# IR_Control.net
KiCad netlist of a schematic drawn in Altium Designer
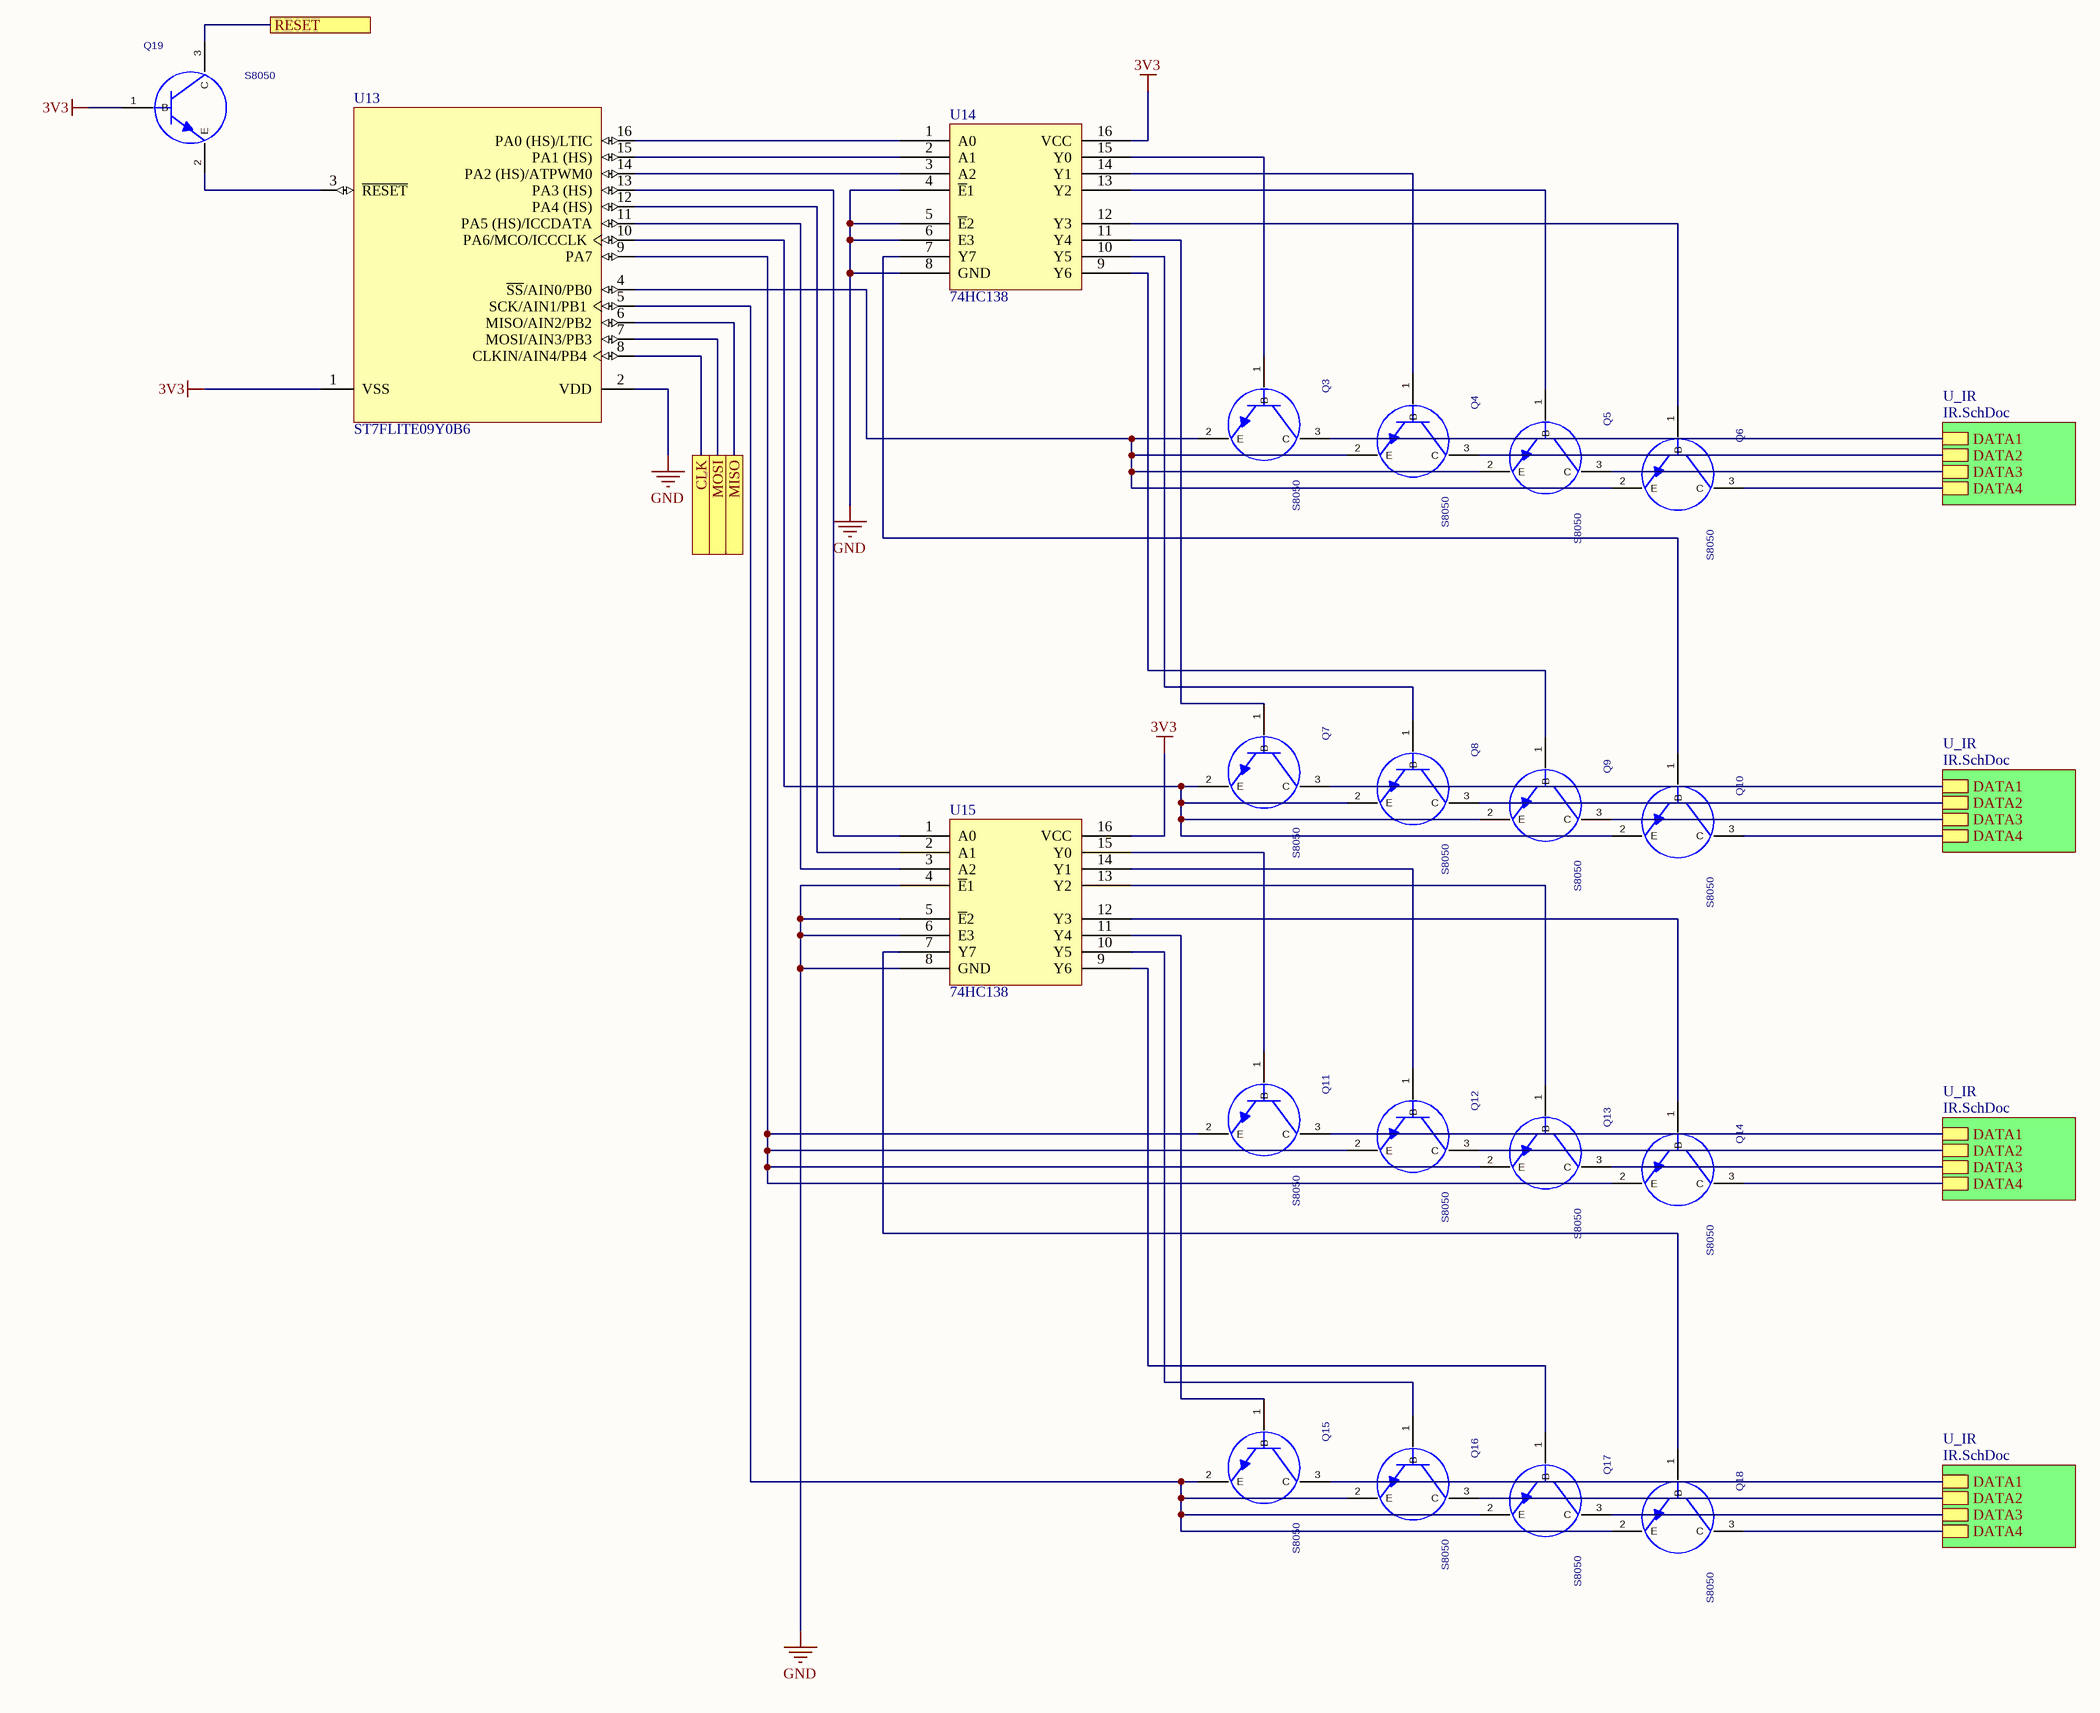
[diagram p0: IR_Control.SchDoc]

(export (version "E")
  (design (tool "Eeschema 10.0.6"))
  (components
    (comp (ref "Q3")
      (value "S8050")
      (footprint "SOT-23")
      (description "NPN")
      (libsource (lib "MINI-V3") (part "S8050"))
    )
    (comp (ref "Q4")
      (value "S8050")
      (footprint "SOT-23")
      (description "NPN")
      (libsource (lib "MINI-V3") (part "S8050"))
    )
    (comp (ref "Q5")
      (value "S8050")
      (footprint "SOT-23")
      (description "NPN")
      (libsource (lib "MINI-V3") (part "S8050"))
    )
    (comp (ref "Q6")
      (value "S8050")
      (footprint "SOT-23")
      (description "NPN")
      (libsource (lib "MINI-V3") (part "S8050"))
    )
    (comp (ref "Q7")
      (value "S8050")
      (footprint "SOT-23")
      (description "NPN")
      (libsource (lib "MINI-V3") (part "S8050"))
    )
    (comp (ref "Q8")
      (value "S8050")
      (footprint "SOT-23")
      (description "NPN")
      (libsource (lib "MINI-V3") (part "S8050"))
    )
    (comp (ref "Q9")
      (value "S8050")
      (footprint "SOT-23")
      (description "NPN")
      (libsource (lib "MINI-V3") (part "S8050"))
    )
    (comp (ref "Q10")
      (value "S8050")
      (footprint "SOT-23")
      (description "NPN")
      (libsource (lib "MINI-V3") (part "S8050"))
    )
    (comp (ref "Q11")
      (value "S8050")
      (footprint "SOT-23")
      (description "NPN")
      (libsource (lib "MINI-V3") (part "S8050"))
    )
    (comp (ref "Q12")
      (value "S8050")
      (footprint "SOT-23")
      (description "NPN")
      (libsource (lib "MINI-V3") (part "S8050"))
    )
    (comp (ref "Q13")
      (value "S8050")
      (footprint "SOT-23")
      (description "NPN")
      (libsource (lib "MINI-V3") (part "S8050"))
    )
    (comp (ref "Q14")
      (value "S8050")
      (footprint "SOT-23")
      (description "NPN")
      (libsource (lib "MINI-V3") (part "S8050"))
    )
    (comp (ref "Q15")
      (value "S8050")
      (footprint "SOT-23")
      (description "NPN")
      (libsource (lib "MINI-V3") (part "S8050"))
    )
    (comp (ref "Q16")
      (value "S8050")
      (footprint "SOT-23")
      (description "NPN")
      (libsource (lib "MINI-V3") (part "S8050"))
    )
    (comp (ref "Q17")
      (value "S8050")
      (footprint "SOT-23")
      (description "NPN")
      (libsource (lib "MINI-V3") (part "S8050"))
    )
    (comp (ref "Q18")
      (value "S8050")
      (footprint "SOT-23")
      (description "NPN")
      (libsource (lib "MINI-V3") (part "S8050"))
    )
    (comp (ref "Q19")
      (value "S8050")
      (footprint "SOT-23")
      (description "NPN")
      (libsource (lib "MINI-V3") (part "S8050"))
    )
    (comp (ref "U13")
      (value "ST7FLITE09Y0B6")
      (footprint "PDIP16")
      (fields (field (name "PUBLISHER") "Altium Limited"))
      (libsource (lib "ST Microcontroller 8-Bit") (part "ST7FLITE09Y0B6"))
    )
    (comp (ref "U14") (value "74HC138") (footprint "74HC138") (libsource (lib "Inte_Car") (part "74HC138")))
    (comp (ref "U15") (value "74HC138") (footprint "74HC138") (libsource (lib "Inte_Car") (part "74HC138")))
  )
  (nets
    (net (code "1") (name "/CLK") (class "Default")
      (node (ref "U13") (pin "8") (pinfunction "CLKIN/AIN4/PB4_8") (pintype "bidirectional"))
    )
    (net (code "2") (name "/DATA1") (class "Default")
      (node (ref "Q3") (pin "3") (pinfunction "C_3") (pintype "passive"))
    )
    (net (code "3") (name "/DATA1_1") (class "Default")
      (node (ref "Q11") (pin "3") (pinfunction "C_3") (pintype "passive"))
    )
    (net (code "4") (name "/DATA1_2") (class "Default")
      (node (ref "Q15") (pin "3") (pinfunction "C_3") (pintype "passive"))
    )
    (net (code "5") (name "/DATA1_3") (class "Default")
      (node (ref "Q7") (pin "3") (pinfunction "C_3") (pintype "passive"))
    )
    (net (code "6") (name "/DATA2") (class "Default")
      (node (ref "Q4") (pin "3") (pinfunction "C_3") (pintype "passive"))
    )
    (net (code "7") (name "/DATA2_1") (class "Default")
      (node (ref "Q12") (pin "3") (pinfunction "C_3") (pintype "passive"))
    )
    (net (code "8") (name "/DATA2_2") (class "Default")
      (node (ref "Q16") (pin "3") (pinfunction "C_3") (pintype "passive"))
    )
    (net (code "9") (name "/DATA2_3") (class "Default")
      (node (ref "Q8") (pin "3") (pinfunction "C_3") (pintype "passive"))
    )
    (net (code "10") (name "/DATA3") (class "Default")
      (node (ref "Q9") (pin "3") (pinfunction "C_3") (pintype "passive"))
    )
    (net (code "11") (name "/DATA3_1") (class "Default")
      (node (ref "Q13") (pin "3") (pinfunction "C_3") (pintype "passive"))
    )
    (net (code "12") (name "/DATA3_2") (class "Default")
      (node (ref "Q17") (pin "3") (pinfunction "C_3") (pintype "passive"))
    )
    (net (code "13") (name "/DATA3_3") (class "Default")
      (node (ref "Q5") (pin "3") (pinfunction "C_3") (pintype "passive"))
    )
    (net (code "14") (name "/DATA4") (class "Default")
      (node (ref "Q6") (pin "3") (pinfunction "C_3") (pintype "passive"))
    )
    (net (code "15") (name "/DATA4_1") (class "Default")
      (node (ref "Q14") (pin "3") (pinfunction "C_3") (pintype "passive"))
    )
    (net (code "16") (name "/DATA4_2") (class "Default")
      (node (ref "Q18") (pin "3") (pinfunction "C_3") (pintype "passive"))
    )
    (net (code "17") (name "/DATA4_3") (class "Default")
      (node (ref "Q10") (pin "3") (pinfunction "C_3") (pintype "passive"))
    )
    (net (code "18") (name "/MISO") (class "Default")
      (node (ref "U13") (pin "6") (pinfunction "MISO/AIN2/PB2_6") (pintype "bidirectional"))
    )
    (net (code "19") (name "/MOSI") (class "Default")
      (node (ref "U13") (pin "7") (pinfunction "MOSI/AIN3/PB3_7") (pintype "bidirectional"))
    )
    (net (code "20") (name "/RESET") (class "Default")
      (node (ref "Q19") (pin "3") (pinfunction "C_3") (pintype "passive"))
    )
    (net (code "21") (name "3V3") (class "Default")
      (node (ref "Q19") (pin "1") (pinfunction "B_1") (pintype "passive"))
      (node (ref "U13") (pin "1") (pinfunction "VSS_1") (pintype "power_in"))
      (node (ref "U14") (pin "16") (pinfunction "VCC_16") (pintype "passive"))
      (node (ref "U15") (pin "16") (pinfunction "VCC_16") (pintype "passive"))
    )
    (net (code "22") (name "GND") (class "Default")
      (node (ref "U13") (pin "2") (pinfunction "VDD_2") (pintype "power_in"))
      (node (ref "U14") (pin "4") (pinfunction "~{E}1_4") (pintype "passive"))
      (node (ref "U14") (pin "5") (pinfunction "~{E}2_5") (pintype "passive"))
      (node (ref "U14") (pin "6") (pinfunction "E3_6") (pintype "passive"))
      (node (ref "U14") (pin "8") (pinfunction "GND_8") (pintype "passive"))
      (node (ref "U15") (pin "4") (pinfunction "~{E}1_4") (pintype "passive"))
      (node (ref "U15") (pin "5") (pinfunction "~{E}2_5") (pintype "passive"))
      (node (ref "U15") (pin "6") (pinfunction "E3_6") (pintype "passive"))
      (node (ref "U15") (pin "8") (pinfunction "GND_8") (pintype "passive"))
    )
    (net (code "23") (name "Net-(Q3-B)") (class "Default")
      (node (ref "Q3") (pin "1") (pinfunction "B_1") (pintype "passive"))
      (node (ref "U14") (pin "15") (pinfunction "Y0_15") (pintype "passive"))
    )
    (net (code "24") (name "Net-(Q3-E)") (class "Default")
      (node (ref "Q3") (pin "2") (pinfunction "E_2") (pintype "passive"))
      (node (ref "Q4") (pin "2") (pinfunction "E_2") (pintype "passive"))
      (node (ref "Q5") (pin "2") (pinfunction "E_2") (pintype "passive"))
      (node (ref "Q6") (pin "2") (pinfunction "E_2") (pintype "passive"))
      (node (ref "U13") (pin "4") (pinfunction "~{SS}/AIN0/PB0_4") (pintype "bidirectional"))
    )
    (net (code "25") (name "Net-(Q4-B)") (class "Default")
      (node (ref "Q4") (pin "1") (pinfunction "B_1") (pintype "passive"))
      (node (ref "U14") (pin "14") (pinfunction "Y1_14") (pintype "passive"))
    )
    (net (code "26") (name "Net-(Q5-B)") (class "Default")
      (node (ref "Q5") (pin "1") (pinfunction "B_1") (pintype "passive"))
      (node (ref "U14") (pin "13") (pinfunction "Y2_13") (pintype "passive"))
    )
    (net (code "27") (name "Net-(Q6-B)") (class "Default")
      (node (ref "Q6") (pin "1") (pinfunction "B_1") (pintype "passive"))
      (node (ref "U14") (pin "12") (pinfunction "Y3_12") (pintype "passive"))
    )
    (net (code "28") (name "Net-(Q7-B)") (class "Default")
      (node (ref "Q7") (pin "1") (pinfunction "B_1") (pintype "passive"))
      (node (ref "U14") (pin "11") (pinfunction "Y4_11") (pintype "passive"))
    )
    (net (code "29") (name "Net-(Q8-B)") (class "Default")
      (node (ref "Q8") (pin "1") (pinfunction "B_1") (pintype "passive"))
      (node (ref "U14") (pin "10") (pinfunction "Y5_10") (pintype "passive"))
    )
    (net (code "30") (name "Net-(Q9-B)") (class "Default")
      (node (ref "Q9") (pin "1") (pinfunction "B_1") (pintype "passive"))
      (node (ref "U14") (pin "9") (pinfunction "Y6_9") (pintype "passive"))
    )
    (net (code "31") (name "Net-(Q10-B)") (class "Default")
      (node (ref "Q10") (pin "1") (pinfunction "B_1") (pintype "passive"))
      (node (ref "U14") (pin "7") (pinfunction "Y7_7") (pintype "passive"))
    )
    (net (code "32") (name "Net-(Q10-E)") (class "Default")
      (node (ref "Q10") (pin "2") (pinfunction "E_2") (pintype "passive"))
      (node (ref "Q7") (pin "2") (pinfunction "E_2") (pintype "passive"))
      (node (ref "Q8") (pin "2") (pinfunction "E_2") (pintype "passive"))
      (node (ref "Q9") (pin "2") (pinfunction "E_2") (pintype "passive"))
      (node (ref "U13") (pin "10") (pinfunction "PA6/MCO/ICCCLK_10") (pintype "bidirectional"))
    )
    (net (code "33") (name "Net-(Q11-B)") (class "Default")
      (node (ref "Q11") (pin "1") (pinfunction "B_1") (pintype "passive"))
      (node (ref "U15") (pin "15") (pinfunction "Y0_15") (pintype "passive"))
    )
    (net (code "34") (name "Net-(Q11-E)") (class "Default")
      (node (ref "Q11") (pin "2") (pinfunction "E_2") (pintype "passive"))
      (node (ref "Q12") (pin "2") (pinfunction "E_2") (pintype "passive"))
      (node (ref "Q13") (pin "2") (pinfunction "E_2") (pintype "passive"))
      (node (ref "Q14") (pin "2") (pinfunction "E_2") (pintype "passive"))
      (node (ref "U13") (pin "9") (pinfunction "PA7_9") (pintype "bidirectional"))
    )
    (net (code "35") (name "Net-(Q12-B)") (class "Default")
      (node (ref "Q12") (pin "1") (pinfunction "B_1") (pintype "passive"))
      (node (ref "U15") (pin "14") (pinfunction "Y1_14") (pintype "passive"))
    )
    (net (code "36") (name "Net-(Q13-B)") (class "Default")
      (node (ref "Q13") (pin "1") (pinfunction "B_1") (pintype "passive"))
      (node (ref "U15") (pin "13") (pinfunction "Y2_13") (pintype "passive"))
    )
    (net (code "37") (name "Net-(Q14-B)") (class "Default")
      (node (ref "Q14") (pin "1") (pinfunction "B_1") (pintype "passive"))
      (node (ref "U15") (pin "12") (pinfunction "Y3_12") (pintype "passive"))
    )
    (net (code "38") (name "Net-(Q15-B)") (class "Default")
      (node (ref "Q15") (pin "1") (pinfunction "B_1") (pintype "passive"))
      (node (ref "U15") (pin "11") (pinfunction "Y4_11") (pintype "passive"))
    )
    (net (code "39") (name "Net-(Q15-E)") (class "Default")
      (node (ref "Q15") (pin "2") (pinfunction "E_2") (pintype "passive"))
      (node (ref "Q16") (pin "2") (pinfunction "E_2") (pintype "passive"))
      (node (ref "Q17") (pin "2") (pinfunction "E_2") (pintype "passive"))
      (node (ref "Q18") (pin "2") (pinfunction "E_2") (pintype "passive"))
      (node (ref "U13") (pin "5") (pinfunction "SCK/AIN1/PB1_5") (pintype "bidirectional"))
    )
    (net (code "40") (name "Net-(Q16-B)") (class "Default")
      (node (ref "Q16") (pin "1") (pinfunction "B_1") (pintype "passive"))
      (node (ref "U15") (pin "10") (pinfunction "Y5_10") (pintype "passive"))
    )
    (net (code "41") (name "Net-(Q17-B)") (class "Default")
      (node (ref "Q17") (pin "1") (pinfunction "B_1") (pintype "passive"))
      (node (ref "U15") (pin "9") (pinfunction "Y6_9") (pintype "passive"))
    )
    (net (code "42") (name "Net-(Q18-B)") (class "Default")
      (node (ref "Q18") (pin "1") (pinfunction "B_1") (pintype "passive"))
      (node (ref "U15") (pin "7") (pinfunction "Y7_7") (pintype "passive"))
    )
    (net (code "43") (name "Net-(Q19-E)") (class "Default")
      (node (ref "Q19") (pin "2") (pinfunction "E_2") (pintype "passive"))
      (node (ref "U13") (pin "3") (pinfunction "~{RESET}_3") (pintype "bidirectional"))
    )
    (net (code "44") (name "Net-(U13-PA0_(HS){slash}LTIC)") (class "Default")
      (node (ref "U13") (pin "16") (pinfunction "PA0_(HS)/LTIC_16") (pintype "bidirectional"))
      (node (ref "U14") (pin "1") (pinfunction "A0_1") (pintype "passive"))
    )
    (net (code "45") (name "Net-(U13-PA1_(HS))") (class "Default")
      (node (ref "U13") (pin "15") (pinfunction "PA1_(HS)_15") (pintype "bidirectional"))
      (node (ref "U14") (pin "2") (pinfunction "A1_2") (pintype "passive"))
    )
    (net (code "46") (name "Net-(U13-PA2_(HS){slash}ATPWM0)") (class "Default")
      (node (ref "U13") (pin "14") (pinfunction "PA2_(HS)/ATPWM0_14") (pintype "bidirectional"))
      (node (ref "U14") (pin "3") (pinfunction "A2_3") (pintype "passive"))
    )
    (net (code "47") (name "Net-(U13-PA3_(HS))") (class "Default")
      (node (ref "U13") (pin "13") (pinfunction "PA3_(HS)_13") (pintype "bidirectional"))
      (node (ref "U15") (pin "1") (pinfunction "A0_1") (pintype "passive"))
    )
    (net (code "48") (name "Net-(U13-PA4_(HS))") (class "Default")
      (node (ref "U13") (pin "12") (pinfunction "PA4_(HS)_12") (pintype "bidirectional"))
      (node (ref "U15") (pin "2") (pinfunction "A1_2") (pintype "passive"))
    )
    (net (code "49") (name "Net-(U13-PA5_(HS){slash}ICCDATA)") (class "Default")
      (node (ref "U13") (pin "11") (pinfunction "PA5_(HS)/ICCDATA_11") (pintype "bidirectional"))
      (node (ref "U15") (pin "3") (pinfunction "A2_3") (pintype "passive"))
    )
  )
)
